# Current_measurement_circuit.net
KiCad netlist of a schematic drawn in Altium Designer
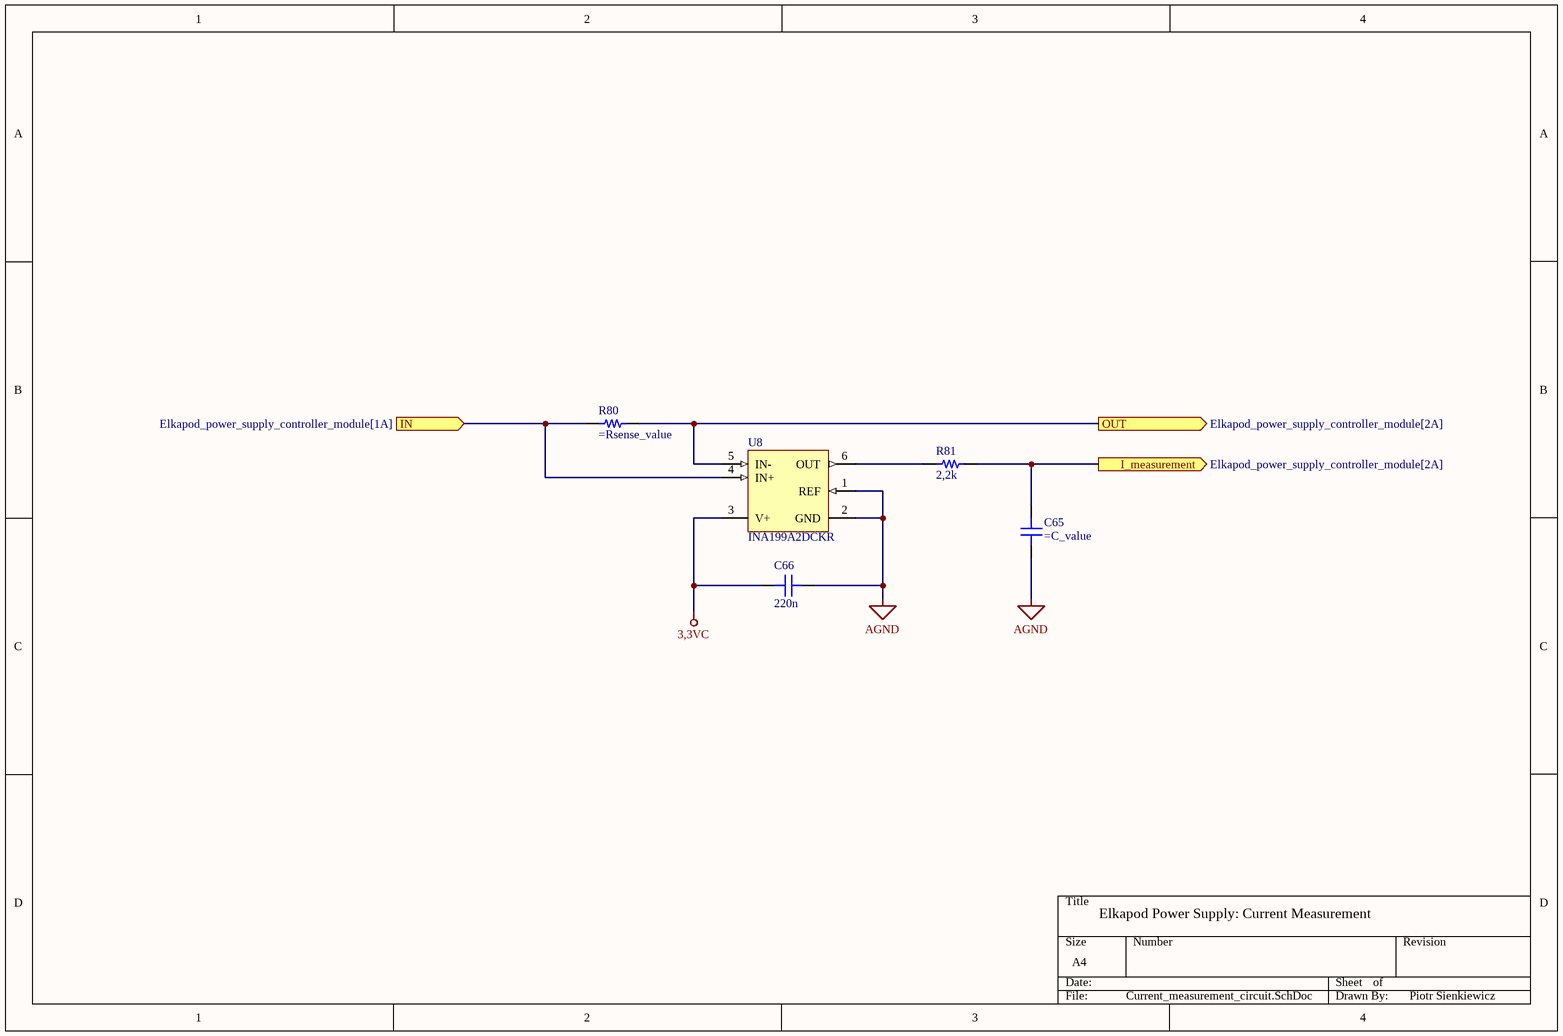
[diagram p0: Current_measurement_circuit.SchDoc]

(export (version "E")
  (design (tool "Eeschema 10.0.6"))
  (components
    (comp (ref "C65")
      (value "~")
      (footprint "CAP 0603_1608")
      (description "CAP CER ??uF 35V X5R 0603")
      (fields (field (name "PART NUMBER") "C0603C272F3GAC7867") (field (name "MANUFACTURER") "KEMET"))
      (libsource (lib "Celestial Altium Library - altium_library") (part "Capacitor"))
    )
    (comp (ref "C66")
      (value "220n")
      (footprint "CAP 0603_1608")
      (description "CAP CER 220nF 25V X5R 0603")
      (fields (field (name "PART NUMBER") "C0603C272F3GAC7867") (field (name "MANUFACTURER") "KEMET"))
      (libsource (lib "Celestial Altium Library - altium_library") (part "Capacitor"))
    )
    (comp (ref "R80")
      (value "~")
      (footprint "STACKPOLE CSM2512")
      (description "RES 1% 3W 2512")
      (fields
        (field (name "PART NUMBER") "CSM2512FT20L0")
        (field (name "MANUFACTURER") "Stackpole Electronics Inc")
      )
      (libsource (lib "Celestial Altium Library - altium_library") (part "Resistor"))
    )
    (comp (ref "R81")
      (value "2,2k")
      (footprint "RES 0603_1608")
      (description "RES 2,2K OHM 1% 0,1W 0603")
      (fields
        (field (name "PART NUMBER") "RNCS0603BKE10K0")
        (field (name "MANUFACTURER") "Stackpole Electronics Inc")
      )
      (libsource (lib "Celestial Altium Library - altium_library") (part "Resistor"))
    )
    (comp (ref "U8")
      (value "INA199A2DCKR")
      (footprint "DCK0006A_N")
      (libsource (lib "Altium Content Vault") (part "TI-INA199A2DCK6"))
    )
  )
  (nets
    (net (code "1") (name "/IN") (class "Default")
      (node (ref "R80") (pin "2") (pinfunction "2_2") (pintype "passive"))
      (node (ref "U8") (pin "4") (pinfunction "IN+_4") (pintype "input"))
    )
    (net (code "2") (name "/I_measurement") (class "Default")
      (node (ref "C65") (pin "2") (pinfunction "2_2") (pintype "passive"))
      (node (ref "R81") (pin "2") (pinfunction "2_2") (pintype "passive"))
    )
    (net (code "3") (name "/OUT") (class "Default")
      (node (ref "R80") (pin "1") (pinfunction "1_1") (pintype "passive"))
      (node (ref "U8") (pin "5") (pinfunction "IN-_5") (pintype "input"))
    )
    (net (code "4") (name "3,3VC") (class "Default")
      (node (ref "C66") (pin "2") (pinfunction "2_2") (pintype "passive"))
      (node (ref "U8") (pin "3") (pinfunction "V+_3") (pintype "power_in"))
    )
    (net (code "5") (name "AGND") (class "Default")
      (node (ref "C65") (pin "1") (pinfunction "1_1") (pintype "passive"))
      (node (ref "C66") (pin "1") (pinfunction "1_1") (pintype "passive"))
      (node (ref "U8") (pin "1") (pinfunction "REF_1") (pintype "input"))
      (node (ref "U8") (pin "2") (pinfunction "GND_2") (pintype "power_in"))
    )
    (net (code "6") (name "Net-(U8-OUT)") (class "Default")
      (node (ref "R81") (pin "1") (pinfunction "1_1") (pintype "passive"))
      (node (ref "U8") (pin "6") (pinfunction "OUT_6") (pintype "output"))
    )
  )
)
